# MCU.net
KiCad netlist of a schematic drawn in Altium Designer
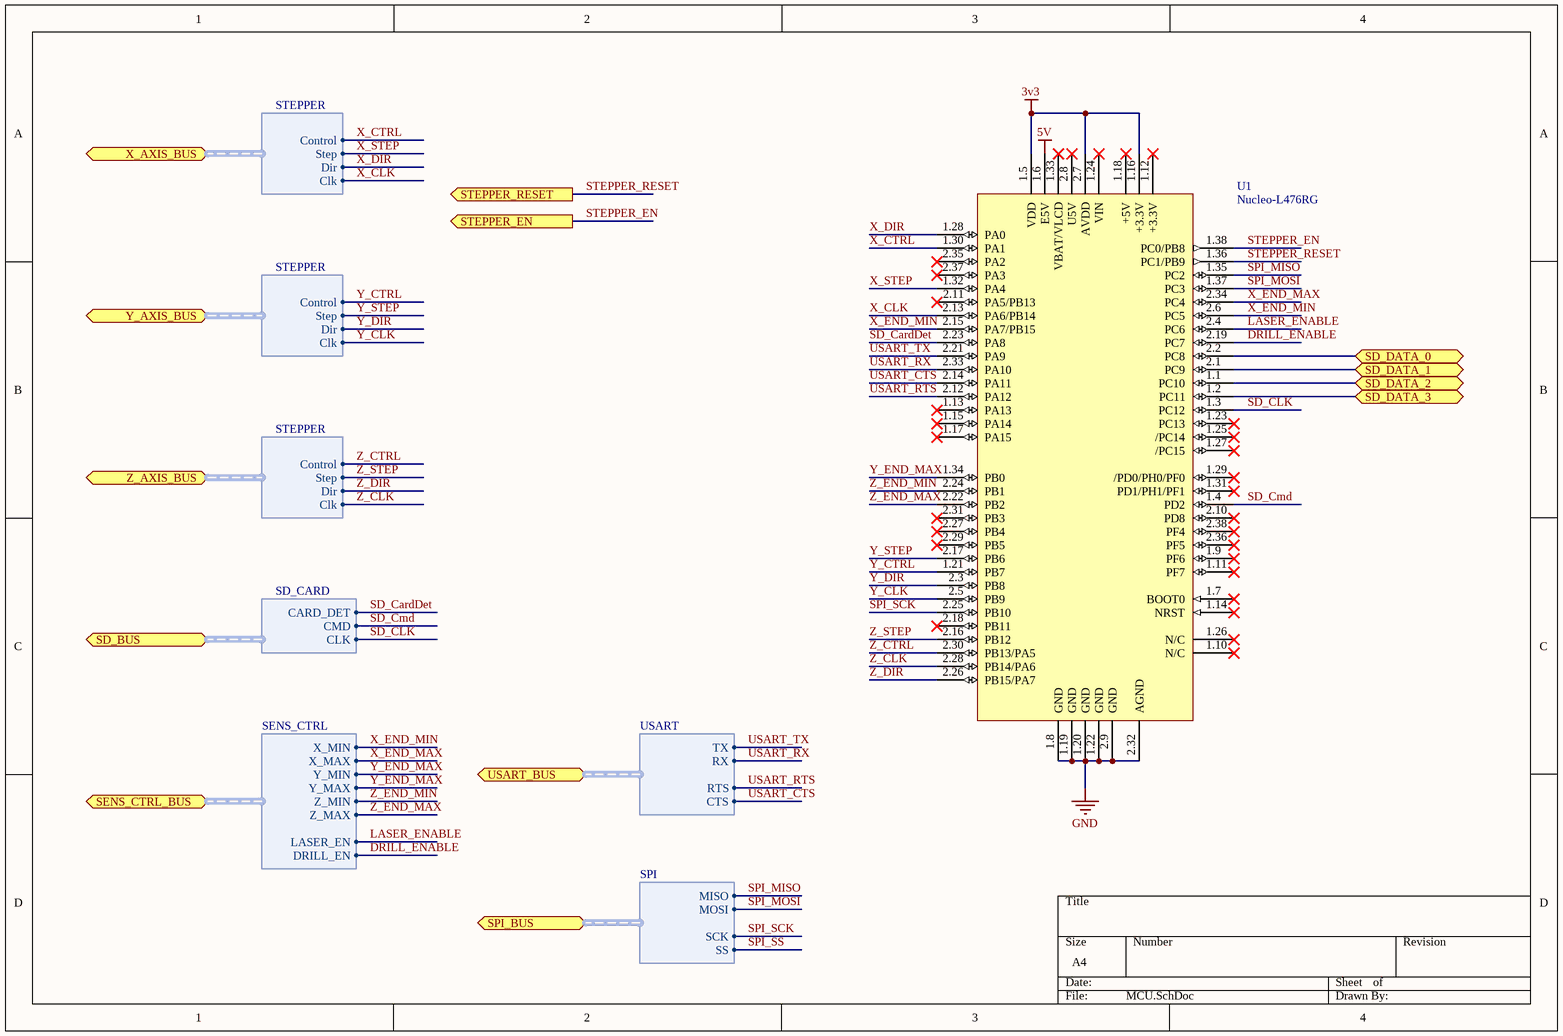
[diagram p0: MCU.SchDoc]

(export (version "E")
  (design (tool "Eeschema 10.0.6"))
  (components
    (comp (ref "U1")
      (value "Nucleo-L476RG")
      (footprint "NUCLEO--F103RB")
      (libsource (lib "INSA") (part "Nucleo-F103RB"))
    )
  )
  (nets
    (net (code "6") (name "/DRILL_ENABLE") (class "Default")
      (node (ref "U1") (pin "2.19") (pinfunction "PC7_2.19") (pintype "bidirectional"))
    )
    (net (code "7") (name "/LASER_ENABLE") (class "Default")
      (node (ref "U1") (pin "2.4") (pinfunction "PC6_2.4") (pintype "bidirectional"))
    )
    (net (code "8") (name "/SD_CLK") (class "Default")
      (node (ref "U1") (pin "1.3") (pinfunction "PC12_1.3") (pintype "bidirectional"))
    )
    (net (code "9") (name "/SD_CardDet") (class "Default")
      (node (ref "U1") (pin "2.23") (pinfunction "PA8_2.23") (pintype "bidirectional"))
    )
    (net (code "10") (name "/SD_Cmd") (class "Default")
      (node (ref "U1") (pin "1.4") (pinfunction "PD2_1.4") (pintype "bidirectional"))
    )
    (net (code "11") (name "/SD_DATA_0") (class "Default")
      (node (ref "U1") (pin "2.2") (pinfunction "PC8_2.2") (pintype "bidirectional"))
    )
    (net (code "12") (name "/SD_DATA_1") (class "Default")
      (node (ref "U1") (pin "2.1") (pinfunction "PC9_2.1") (pintype "bidirectional"))
    )
    (net (code "13") (name "/SD_DATA_2") (class "Default")
      (node (ref "U1") (pin "1.1") (pinfunction "PC10_1.1") (pintype "bidirectional"))
    )
    (net (code "14") (name "/SD_DATA_3") (class "Default")
      (node (ref "U1") (pin "1.2") (pinfunction "PC11_1.2") (pintype "bidirectional"))
    )
    (net (code "15") (name "/SPI_MISO") (class "Default")
      (node (ref "U1") (pin "1.35") (pinfunction "PC2_1.35") (pintype "bidirectional"))
    )
    (net (code "16") (name "/SPI_MOSI") (class "Default")
      (node (ref "U1") (pin "1.37") (pinfunction "PC3_1.37") (pintype "bidirectional"))
    )
    (net (code "17") (name "/SPI_SCK") (class "Default")
      (node (ref "U1") (pin "2.25") (pinfunction "PB10_2.25") (pintype "bidirectional"))
    )
    (net (code "19") (name "/STEPPER_EN") (class "Default")
      (node (ref "U1") (pin "1.38") (pinfunction "PC0/PB8_1.38") (pintype "output"))
    )
    (net (code "20") (name "/STEPPER_RESET") (class "Default")
      (node (ref "U1") (pin "1.36") (pinfunction "PC1/PB9_1.36") (pintype "output"))
    )
    (net (code "21") (name "/USART_CTS") (class "Default")
      (node (ref "U1") (pin "2.14") (pinfunction "PA11_2.14") (pintype "bidirectional"))
    )
    (net (code "22") (name "/USART_RTS") (class "Default")
      (node (ref "U1") (pin "2.12") (pinfunction "PA12_2.12") (pintype "bidirectional"))
    )
    (net (code "23") (name "/USART_RX") (class "Default")
      (node (ref "U1") (pin "2.33") (pinfunction "PA10_2.33") (pintype "bidirectional"))
    )
    (net (code "24") (name "/USART_TX") (class "Default")
      (node (ref "U1") (pin "2.21") (pinfunction "PA9_2.21") (pintype "bidirectional"))
    )
    (net (code "25") (name "/X_CLK") (class "Default")
      (node (ref "U1") (pin "2.13") (pinfunction "PA6/PB14_2.13") (pintype "bidirectional"))
    )
    (net (code "26") (name "/X_CTRL") (class "Default")
      (node (ref "U1") (pin "1.30") (pinfunction "PA1_1.30") (pintype "bidirectional"))
    )
    (net (code "27") (name "/X_DIR") (class "Default")
      (node (ref "U1") (pin "1.28") (pinfunction "PA0_1.28") (pintype "bidirectional"))
    )
    (net (code "28") (name "/X_END_MAX") (class "Default")
      (node (ref "U1") (pin "2.34") (pinfunction "PC4_2.34") (pintype "bidirectional"))
    )
    (net (code "29") (name "/X_END_MIN") (class "Default")
      (node (ref "U1") (pin "2.15") (pinfunction "PA7/PB15_2.15") (pintype "bidirectional"))
      (node (ref "U1") (pin "2.6") (pinfunction "PC5_2.6") (pintype "bidirectional"))
    )
    (net (code "30") (name "/X_STEP") (class "Default")
      (node (ref "U1") (pin "1.32") (pinfunction "PA4_1.32") (pintype "bidirectional"))
    )
    (net (code "31") (name "/Y_CLK") (class "Default")
      (node (ref "U1") (pin "2.5") (pinfunction "PB9_2.5") (pintype "bidirectional"))
    )
    (net (code "32") (name "/Y_CTRL") (class "Default")
      (node (ref "U1") (pin "1.21") (pinfunction "PB7_1.21") (pintype "bidirectional"))
    )
    (net (code "33") (name "/Y_DIR") (class "Default")
      (node (ref "U1") (pin "2.3") (pinfunction "PB8_2.3") (pintype "bidirectional"))
    )
    (net (code "34") (name "/Y_END_MAX") (class "Default")
      (node (ref "U1") (pin "1.34") (pinfunction "PB0_1.34") (pintype "bidirectional"))
    )
    (net (code "35") (name "/Y_STEP") (class "Default")
      (node (ref "U1") (pin "2.17") (pinfunction "PB6_2.17") (pintype "bidirectional"))
    )
    (net (code "36") (name "/Z_CLK") (class "Default")
      (node (ref "U1") (pin "2.28") (pinfunction "PB14/PA6_2.28") (pintype "bidirectional"))
    )
    (net (code "37") (name "/Z_CTRL") (class "Default")
      (node (ref "U1") (pin "2.30") (pinfunction "PB13/PA5_2.30") (pintype "bidirectional"))
    )
    (net (code "38") (name "/Z_DIR") (class "Default")
      (node (ref "U1") (pin "2.26") (pinfunction "PB15/PA7_2.26") (pintype "bidirectional"))
    )
    (net (code "39") (name "/Z_END_MAX") (class "Default")
      (node (ref "U1") (pin "2.22") (pinfunction "PB2_2.22") (pintype "bidirectional"))
    )
    (net (code "40") (name "/Z_END_MIN") (class "Default")
      (node (ref "U1") (pin "2.24") (pinfunction "PB1_2.24") (pintype "bidirectional"))
    )
    (net (code "41") (name "/Z_STEP") (class "Default")
      (node (ref "U1") (pin "2.16") (pinfunction "PB12_2.16") (pintype "bidirectional"))
    )
    (net (code "47") (name "3v3") (class "Default")
      (node (ref "U1") (pin "1.16") (pinfunction "+3.3V_1.16") (pintype "power_in"))
      (node (ref "U1") (pin "1.5") (pinfunction "VDD_1.5") (pintype "power_in"))
      (node (ref "U1") (pin "2.7") (pinfunction "AVDD_2.7") (pintype "power_in"))
    )
    (net (code "48") (name "5V") (class "Default")
      (node (ref "U1") (pin "1.6") (pinfunction "E5V_1.6") (pintype "power_in"))
    )
    (net (code "49") (name "GND") (class "Default")
      (node (ref "U1") (pin "1.19") (pinfunction "GND_1.19") (pintype "power_in"))
      (node (ref "U1") (pin "1.20") (pinfunction "GND_1.20") (pintype "power_in"))
      (node (ref "U1") (pin "1.22") (pinfunction "GND_1.22") (pintype "power_in"))
      (node (ref "U1") (pin "1.8") (pinfunction "GND_1.8") (pintype "power_in"))
      (node (ref "U1") (pin "2.32") (pinfunction "AGND_2.32") (pintype "power_in"))
      (node (ref "U1") (pin "2.9") (pinfunction "GND_2.9") (pintype "power_in"))
    )
    (net (code "50") (name "unconnected-(U1-+3.3V-Pad1.12)") (class "Default")
      (node (ref "U1") (pin "1.12") (pinfunction "+3.3V_1.12") (pintype "power_in+no_connect"))
    )
    (net (code "51") (name "unconnected-(U1-+5V-Pad1.18)") (class "Default")
      (node (ref "U1") (pin "1.18") (pinfunction "+5V_1.18") (pintype "power_in+no_connect"))
    )
    (net (code "52") (name "unconnected-(U1-BOOT0-Pad1.7)") (class "Default")
      (node (ref "U1") (pin "1.7") (pinfunction "BOOT0_1.7") (pintype "input+no_connect"))
    )
    (net (code "53") (name "unconnected-(U1-NRST-Pad1.14)") (class "Default")
      (node (ref "U1") (pin "1.14") (pinfunction "NRST_1.14") (pintype "input+no_connect"))
    )
    (net (code "54") (name "unconnected-(U1-N{slash}C-Pad1.10)") (class "Default")
      (node (ref "U1") (pin "1.10") (pinfunction "N/C_1.10") (pintype "passive+no_connect"))
    )
    (net (code "55") (name "unconnected-(U1-N{slash}C-Pad1.26)") (class "Default")
      (node (ref "U1") (pin "1.26") (pinfunction "N/C_1.26") (pintype "passive+no_connect"))
    )
    (net (code "56") (name "unconnected-(U1-PA2-Pad2.35)") (class "Default")
      (node (ref "U1") (pin "2.35") (pinfunction "PA2_2.35") (pintype "bidirectional+no_connect"))
    )
    (net (code "57") (name "unconnected-(U1-PA3-Pad2.37)") (class "Default")
      (node (ref "U1") (pin "2.37") (pinfunction "PA3_2.37") (pintype "bidirectional+no_connect"))
    )
    (net (code "58") (name "unconnected-(U1-PA5{slash}PB13-Pad2.11)") (class "Default")
      (node (ref "U1") (pin "2.11") (pinfunction "PA5/PB13_2.11") (pintype "bidirectional+no_connect"))
    )
    (net (code "59") (name "unconnected-(U1-PA13-Pad1.13)") (class "Default")
      (node (ref "U1") (pin "1.13") (pinfunction "PA13_1.13") (pintype "bidirectional+no_connect"))
    )
    (net (code "60") (name "unconnected-(U1-PA14-Pad1.15)") (class "Default")
      (node (ref "U1") (pin "1.15") (pinfunction "PA14_1.15") (pintype "bidirectional+no_connect"))
    )
    (net (code "61") (name "unconnected-(U1-PA15-Pad1.17)") (class "Default")
      (node (ref "U1") (pin "1.17") (pinfunction "PA15_1.17") (pintype "bidirectional+no_connect"))
    )
    (net (code "62") (name "unconnected-(U1-PB3-Pad2.31)") (class "Default")
      (node (ref "U1") (pin "2.31") (pinfunction "PB3_2.31") (pintype "bidirectional+no_connect"))
    )
    (net (code "63") (name "unconnected-(U1-PB4-Pad2.27)") (class "Default")
      (node (ref "U1") (pin "2.27") (pinfunction "PB4_2.27") (pintype "bidirectional+no_connect"))
    )
    (net (code "64") (name "unconnected-(U1-PB5-Pad2.29)") (class "Default")
      (node (ref "U1") (pin "2.29") (pinfunction "PB5_2.29") (pintype "bidirectional+no_connect"))
    )
    (net (code "65") (name "unconnected-(U1-PB11-Pad2.18)") (class "Default")
      (node (ref "U1") (pin "2.18") (pinfunction "PB11_2.18") (pintype "bidirectional+no_connect"))
    )
    (net (code "66") (name "unconnected-(U1-PC13-Pad1.23)") (class "Default")
      (node (ref "U1") (pin "1.23") (pinfunction "PC13_1.23") (pintype "bidirectional+no_connect"))
    )
    (net (code "67") (name "unconnected-(U1-PD1{slash}PH1{slash}PF1-Pad1.31)") (class "Default")
      (node (ref "U1") (pin "1.31") (pinfunction "PD1/PH1/PF1_1.31") (pintype "bidirectional+no_connect"))
    )
    (net (code "68") (name "unconnected-(U1-PD8-Pad2.10)") (class "Default")
      (node (ref "U1") (pin "2.10") (pinfunction "PD8_2.10") (pintype "bidirectional+no_connect"))
    )
    (net (code "69") (name "unconnected-(U1-PF4-Pad2.38)") (class "Default")
      (node (ref "U1") (pin "2.38") (pinfunction "PF4_2.38") (pintype "bidirectional+no_connect"))
    )
    (net (code "70") (name "unconnected-(U1-PF5-Pad2.36)") (class "Default")
      (node (ref "U1") (pin "2.36") (pinfunction "PF5_2.36") (pintype "bidirectional+no_connect"))
    )
    (net (code "71") (name "unconnected-(U1-PF6-Pad1.9)") (class "Default")
      (node (ref "U1") (pin "1.9") (pinfunction "PF6_1.9") (pintype "bidirectional+no_connect"))
    )
    (net (code "72") (name "unconnected-(U1-PF7-Pad1.11)") (class "Default")
      (node (ref "U1") (pin "1.11") (pinfunction "PF7_1.11") (pintype "bidirectional+no_connect"))
    )
    (net (code "73") (name "unconnected-(U1-U5V-Pad2.8)") (class "Default")
      (node (ref "U1") (pin "2.8") (pinfunction "U5V_2.8") (pintype "power_in+no_connect"))
    )
    (net (code "74") (name "unconnected-(U1-VBAT{slash}VLCD-Pad1.33)") (class "Default")
      (node (ref "U1") (pin "1.33") (pinfunction "VBAT/VLCD_1.33") (pintype "power_in+no_connect"))
    )
    (net (code "75") (name "unconnected-(U1-VIN-Pad1.24)") (class "Default")
      (node (ref "U1") (pin "1.24") (pinfunction "VIN_1.24") (pintype "power_in+no_connect"))
    )
    (net (code "76") (name "unconnected-(U1-{slash}PC14-Pad1.25)") (class "Default")
      (node (ref "U1") (pin "1.25") (pinfunction "/PC14_1.25") (pintype "bidirectional+no_connect"))
    )
    (net (code "77") (name "unconnected-(U1-{slash}PC15-Pad1.27)") (class "Default")
      (node (ref "U1") (pin "1.27") (pinfunction "/PC15_1.27") (pintype "bidirectional+no_connect"))
    )
    (net (code "78") (name "unconnected-(U1-{slash}PD0{slash}PH0{slash}PF0-Pad1.29)") (class "Default")
      (node (ref "U1") (pin "1.29") (pinfunction "/PD0/PH0/PF0_1.29") (pintype "bidirectional+no_connect"))
    )
  )
)
